# Schematic_v8.net
KiCad netlist of a schematic drawn in EAGLE
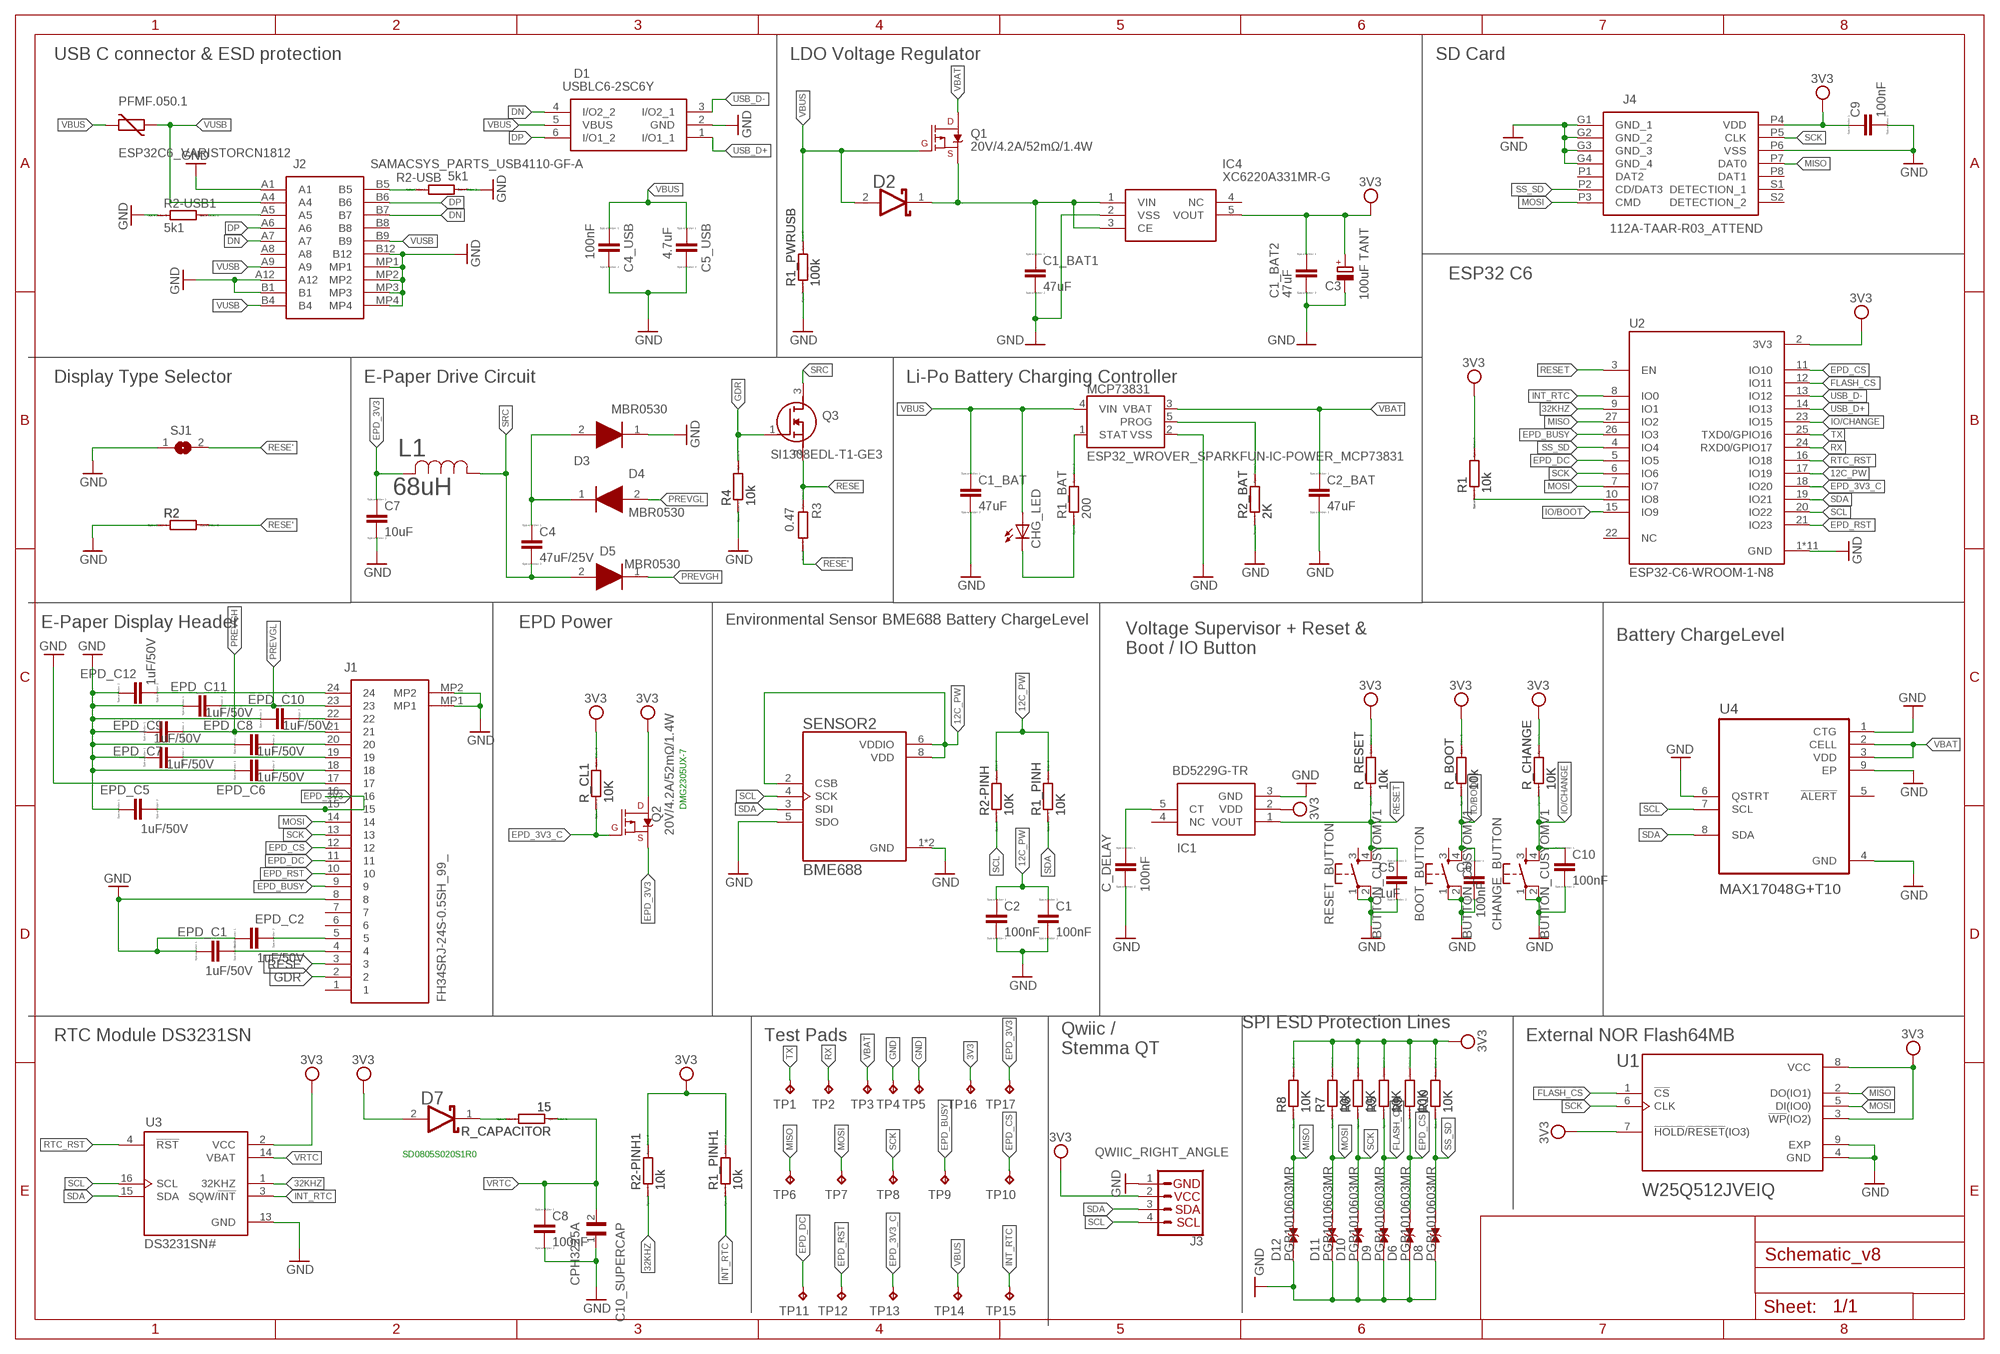
[diagram p0: schematic, sheet 1]

(export (version "E")
  (design (tool "Eeschema 10.0.6"))
  (components
    (comp (ref "BOOT_BUTTON")
      (value "BUTTON_CUSYOMV1")
      (footprint "eagle-import:MYBUTTON")
      (libsource (lib "eagle-import") (part "BUTTON_CUSYOMV1"))
    )
    (comp (ref "C1")
      (value "100nF")
      (footprint "eagle-import:EAGLE-LTSPICE_C0402")
      (libsource (lib "eagle-import") (part "EAGLE-LTSPICE_CC0402"))
    )
    (comp (ref "C1_BAT")
      (value "47uF")
      (footprint "eagle-import:EAGLE-LTSPICE_C0402")
      (libsource (lib "eagle-import") (part "EAGLE-LTSPICE_CC0402"))
    )
    (comp (ref "C1_BAT1")
      (value "47uF")
      (footprint "eagle-import:EAGLE-LTSPICE_C0402")
      (libsource (lib "eagle-import") (part "EAGLE-LTSPICE_CC0402"))
    )
    (comp (ref "C1_BAT2")
      (value "47uF")
      (footprint "eagle-import:EAGLE-LTSPICE_C0402")
      (libsource (lib "eagle-import") (part "EAGLE-LTSPICE_CC0402"))
    )
    (comp (ref "C2")
      (value "100nF")
      (footprint "eagle-import:EAGLE-LTSPICE_C0402")
      (libsource (lib "eagle-import") (part "EAGLE-LTSPICE_CC0402"))
    )
    (comp (ref "C2_BAT")
      (value "47uF")
      (footprint "eagle-import:EAGLE-LTSPICE_C0402")
      (libsource (lib "eagle-import") (part "EAGLE-LTSPICE_CC0402"))
    )
    (comp (ref "C3")
      (value "100uF TANT")
      (footprint "eagle-import:RCL_CT3528")
      (libsource (lib "eagle-import") (part "RCL_CPOL-EUCT3528"))
    )
    (comp (ref "C4")
      (value "47uF/25V")
      (footprint "eagle-import:EAGLE-LTSPICE_C0402")
      (libsource (lib "eagle-import") (part "EAGLE-LTSPICE_CC0402"))
    )
    (comp (ref "C4_USB")
      (value "100nF")
      (footprint "eagle-import:EAGLE-LTSPICE_C0402")
      (libsource (lib "eagle-import") (part "EAGLE-LTSPICE_CC0402"))
    )
    (comp (ref "C5")
      (value "1uF")
      (footprint "eagle-import:EAGLE-LTSPICE_C0402")
      (libsource (lib "eagle-import") (part "EAGLE-LTSPICE_CC0402"))
    )
    (comp (ref "C5_USB")
      (value "4.7uF")
      (footprint "eagle-import:EAGLE-LTSPICE_C0402")
      (libsource (lib "eagle-import") (part "EAGLE-LTSPICE_CC0402"))
    )
    (comp (ref "C6")
      (value "100nF")
      (footprint "eagle-import:EAGLE-LTSPICE_C0402")
      (libsource (lib "eagle-import") (part "EAGLE-LTSPICE_CC0402"))
    )
    (comp (ref "C7")
      (value "10uF")
      (footprint "eagle-import:EAGLE-LTSPICE_C0402")
      (libsource (lib "eagle-import") (part "EAGLE-LTSPICE_CC0402"))
    )
    (comp (ref "C8")
      (value "100nF")
      (footprint "eagle-import:EAGLE-LTSPICE_C0402")
      (libsource (lib "eagle-import") (part "EAGLE-LTSPICE_CC0402"))
    )
    (comp (ref "C9")
      (value "100nF")
      (footprint "eagle-import:EAGLE-LTSPICE_C0402")
      (libsource (lib "eagle-import") (part "EAGLE-LTSPICE_CC0402"))
    )
    (comp (ref "C10")
      (value "100nF")
      (footprint "eagle-import:EAGLE-LTSPICE_C0402")
      (libsource (lib "eagle-import") (part "EAGLE-LTSPICE_CC0402"))
    )
    (comp (ref "C10_SUPERCAP")
      (value "CPH3225A")
      (footprint "eagle-import:CAPCP3225X100N")
      (fields (field (name "MF") "Seiko Instruments"))
      (libsource (lib "eagle-import") (part "CPH3225A"))
    )
    (comp (ref "CHANGE_BUTTON")
      (value "BUTTON_CUSYOMV1")
      (footprint "eagle-import:MYBUTTON")
      (libsource (lib "eagle-import") (part "BUTTON_CUSYOMV1"))
    )
    (comp (ref "CHG_LED")
      (value "ADAFRUIT_LEDCHIP-LED0603")
      (footprint "eagle-import:ADAFRUIT_CHIP-LED0603")
      (libsource (lib "eagle-import") (part "ADAFRUIT_LEDCHIP-LED0603"))
    )
    (comp (ref "C_DELAY")
      (value "100nF")
      (footprint "eagle-import:EAGLE-LTSPICE_C0402")
      (libsource (lib "eagle-import") (part "EAGLE-LTSPICE_CC0402"))
    )
    (comp (ref "D1")
      (value "USBLC6-2SC6Y")
      (footprint "eagle-import:SOT95P280X145-6N")
      (fields (field (name "MF") "STMicroelectronics"))
      (libsource (lib "eagle-import") (part "USBLC6-2SC6Y"))
    )
    (comp (ref "D2")
      (value "SD0805S020S1R0")
      (footprint "eagle-import:ESP32_WROVER_AVX---SD0805S020S1R0_AVX_SD0805S020S1R0_0")
      (fields
        (field (name "DIGIKEY_PART_NUMBER") "478-7800-1-ND")
        (field (name "MF") "AVX")
        (field (name "MOUSER_PART_NUMBER") "581-SD0805S020S1R0")
      )
      (libsource (lib "eagle-import") (part "ESP32_WROVER_AVX---SD0805S020S1R0_AVX_SD0805S020S1R0_0_0AVX_SD0805S020S1R0_0_0"))
    )
    (comp (ref "D3")
      (value "MBR0530")
      (footprint "eagle-import:SOD3716X135N")
      (fields (field (name "MF") "ON Semiconductor"))
      (libsource (lib "eagle-import") (part "MBR0530"))
    )
    (comp (ref "D4")
      (value "MBR0530")
      (footprint "eagle-import:SOD3716X135N")
      (fields (field (name "MF") "ON Semiconductor"))
      (libsource (lib "eagle-import") (part "MBR0530"))
    )
    (comp (ref "D5")
      (value "MBR0530")
      (footprint "eagle-import:SOD3716X135N")
      (fields (field (name "MF") "ON Semiconductor"))
      (libsource (lib "eagle-import") (part "MBR0530"))
    )
    (comp (ref "D6")
      (value "PGB1010603MR")
      (footprint "eagle-import:DIOC1608X36N")
      (fields (field (name "MF") "Littelfuse Inc."))
      (libsource (lib "eagle-import") (part "PGB1010603MR"))
    )
    (comp (ref "D7")
      (value "SD0805S020S1R0")
      (footprint "eagle-import:ESP32_WROVER_AVX---SD0805S020S1R0_AVX_SD0805S020S1R0_0")
      (fields
        (field (name "DIGIKEY_PART_NUMBER") "478-7800-1-ND")
        (field (name "MF") "AVX")
        (field (name "MOUSER_PART_NUMBER") "581-SD0805S020S1R0")
      )
      (libsource (lib "eagle-import") (part "ESP32_WROVER_AVX---SD0805S020S1R0_AVX_SD0805S020S1R0_0_0AVX_SD0805S020S1R0_0_0"))
    )
    (comp (ref "D8")
      (value "PGB1010603MR")
      (footprint "eagle-import:DIOC1608X36N")
      (fields (field (name "MF") "Littelfuse Inc."))
      (libsource (lib "eagle-import") (part "PGB1010603MR"))
    )
    (comp (ref "D9")
      (value "PGB1010603MR")
      (footprint "eagle-import:DIOC1608X36N")
      (fields (field (name "MF") "Littelfuse Inc."))
      (libsource (lib "eagle-import") (part "PGB1010603MR"))
    )
    (comp (ref "D10")
      (value "PGB1010603MR")
      (footprint "eagle-import:DIOC1608X36N")
      (fields (field (name "MF") "Littelfuse Inc."))
      (libsource (lib "eagle-import") (part "PGB1010603MR"))
    )
    (comp (ref "D11")
      (value "PGB1010603MR")
      (footprint "eagle-import:DIOC1608X36N")
      (fields (field (name "MF") "Littelfuse Inc."))
      (libsource (lib "eagle-import") (part "PGB1010603MR"))
    )
    (comp (ref "D12")
      (value "PGB1010603MR")
      (footprint "eagle-import:DIOC1608X36N")
      (fields (field (name "MF") "Littelfuse Inc."))
      (libsource (lib "eagle-import") (part "PGB1010603MR"))
    )
    (comp (ref "EPD_C1")
      (value "1uF/50V")
      (footprint "eagle-import:EAGLE-LTSPICE_C0402")
      (libsource (lib "eagle-import") (part "EAGLE-LTSPICE_CC0402"))
    )
    (comp (ref "EPD_C2")
      (value "1uF/50V")
      (footprint "eagle-import:EAGLE-LTSPICE_C0402")
      (libsource (lib "eagle-import") (part "EAGLE-LTSPICE_CC0402"))
    )
    (comp (ref "EPD_C5")
      (value "1uF/50V")
      (footprint "eagle-import:EAGLE-LTSPICE_C0402")
      (libsource (lib "eagle-import") (part "EAGLE-LTSPICE_CC0402"))
    )
    (comp (ref "EPD_C6")
      (value "1uF/50V")
      (footprint "eagle-import:EAGLE-LTSPICE_C0402")
      (libsource (lib "eagle-import") (part "EAGLE-LTSPICE_CC0402"))
    )
    (comp (ref "EPD_C7")
      (value "1uF/50V")
      (footprint "eagle-import:EAGLE-LTSPICE_C0402")
      (libsource (lib "eagle-import") (part "EAGLE-LTSPICE_CC0402"))
    )
    (comp (ref "EPD_C8")
      (value "1uF/50V")
      (footprint "eagle-import:EAGLE-LTSPICE_C0402")
      (libsource (lib "eagle-import") (part "EAGLE-LTSPICE_CC0402"))
    )
    (comp (ref "EPD_C9")
      (value "1uF/50V")
      (footprint "eagle-import:EAGLE-LTSPICE_C0402")
      (libsource (lib "eagle-import") (part "EAGLE-LTSPICE_CC0402"))
    )
    (comp (ref "EPD_C10")
      (value "1uF/50V")
      (footprint "eagle-import:EAGLE-LTSPICE_C0402")
      (libsource (lib "eagle-import") (part "EAGLE-LTSPICE_CC0402"))
    )
    (comp (ref "EPD_C11")
      (value "1uF/50V")
      (footprint "eagle-import:EAGLE-LTSPICE_C0402")
      (libsource (lib "eagle-import") (part "EAGLE-LTSPICE_CC0402"))
    )
    (comp (ref "EPD_C12")
      (value "1uF/50V")
      (footprint "eagle-import:EAGLE-LTSPICE_C0402")
      (libsource (lib "eagle-import") (part "EAGLE-LTSPICE_CC0402"))
    )
    (comp (ref "IC1")
      (value "BD5229G-TR")
      (footprint "eagle-import:SOT95P280X125-5N")
      (fields (field (name "MOUSER_PART_NUMBER") "755-BD5229G-TR"))
      (libsource (lib "eagle-import") (part "BD5229G-TR"))
    )
    (comp (ref "IC4")
      (value "XC6220A331MR-G")
      (footprint "eagle-import:SOT95P280X120-5N")
      (fields (field (name "MOUSER_PART_NUMBER") "865-XC6220A331MR-G"))
      (libsource (lib "eagle-import") (part "XC6220A331MR-G"))
    )
    (comp (ref "J1")
      (value "FH34SRJ-24S-0.5SH_99_")
      (footprint "eagle-import:FH34SRJ24S05SH99")
      (fields
        (field (name "MANUFACTURER_PART_NUMBER") "FH34SRJ-24S-0.5SH(99)")
        (field (name "MOUSER_PART_NUMBER") "798-FH34SRJ24S05SH99")
      )
      (libsource (lib "eagle-import") (part "FH34SRJ-24S-0.5SH_99_"))
    )
    (comp (ref "J2")
      (value "SAMACSYS_PARTS_USB4110-GF-A")
      (footprint "eagle-import:SAMACSYS_PARTS_USB4110GFA")
      (libsource (lib "eagle-import") (part "SAMACSYS_PARTS_USB4110-GF-ASAM"))
    )
    (comp (ref "J3")
      (value "QWIIC_RIGHT_ANGLE")
      (footprint "eagle-import:JST04_1MM_RA")
      (libsource (lib "eagle-import") (part "QWIIC_CONNECTORJS-1MM"))
    )
    (comp (ref "J4")
      (value "112A-TAAR-R03_ATTEND")
      (footprint "eagle-import:112ATAARR03ATTEND")
      (fields (field (name "MANUFACTURER_PART_NUMBER") "112A-TAAR-R03 ATTEND"))
      (libsource (lib "eagle-import") (part "112A-TAAR-R03_ATTEND"))
    )
    (comp (ref "L1")
      (value "68uH")
      (footprint "eagle-import:IND_4828-WE-TPC_WRE")
      (fields
        (field (name "MANUFACTURER_PART_NUMBER") "744043680")
        (field (name "COPYRIGHT") "Copyright (C) 2024 Ultra Librarian. All rights reserved.")
      )
      (libsource (lib "eagle-import") (part "744043680IND_4828-WE-TPC_WRE"))
    )
    (comp (ref "MCP73831")
      (value "ESP32_WROVER_SPARKFUN-IC-POWER_MCP73831")
      (footprint "eagle-import:ESP32_WROVER_SPARKFUN-IC-POWER_SOT23-5")
      (libsource (lib "eagle-import") (part "ESP32_WROVER_SPARKFUN-IC-POWER_MCP73831"))
    )
    (comp (ref "PFMF.050.1")
      (value "ESP32C6_VARISTORCN1812")
      (footprint "eagle-import:ESP32C6_VARISTOR_CT_CN1812")
      (libsource (lib "eagle-import") (part "ESP32C6_VARISTORCN1812"))
    )
    (comp (ref "Q1")
      (value "20V/4.2A/52mΩ/1.4W")
      (footprint "eagle-import:ESP32_WROVER_SPARKFUN-DISCRETESEMI_SOT23-3")
      (libsource (lib "eagle-import") (part "ESP32_WROVER_SPARKFUN-DISCRETESEMI_MOSFET_PCH-DMG2305UX-7"))
    )
    (comp (ref "Q2")
      (value "20V/4.2A/52mΩ/1.4W")
      (footprint "eagle-import:ESP32_WROVER_SPARKFUN-DISCRETESEMI_SOT23-3")
      (libsource (lib "eagle-import") (part "ESP32_WROVER_SPARKFUN-DISCRETESEMI_MOSFET_PCH-DMG2305UX-7"))
    )
    (comp (ref "Q3")
      (value "SI1308EDL-T1-GE3")
      (footprint "eagle-import:SOT65P210X110-3N")
      (fields (field (name "MF") "Vishay Siliconix"))
      (libsource (lib "eagle-import") (part "SI1308EDL-T1-GE3"))
    )
    (comp (ref "R1")
      (value "10k")
      (footprint "eagle-import:ESP32_WROVER_EAGLE-LTSPICE_R0402")
      (libsource (lib "eagle-import") (part "ESP32_WROVER_EAGLE-LTSPICE_RR0402"))
    )
    (comp (ref "R1_BAT")
      (value "200")
      (footprint "eagle-import:ESP32_WROVER_EAGLE-LTSPICE_R0402")
      (libsource (lib "eagle-import") (part "ESP32_WROVER_EAGLE-LTSPICE_RR0402"))
    )
    (comp (ref "R1_PINH")
      (value "10K")
      (footprint "eagle-import:ESP32_WROVER_EAGLE-LTSPICE_R0402")
      (libsource (lib "eagle-import") (part "ESP32_WROVER_EAGLE-LTSPICE_RR0402"))
    )
    (comp (ref "R1_PINH1")
      (value "10k")
      (footprint "eagle-import:ESP32_WROVER_EAGLE-LTSPICE_R0402")
      (libsource (lib "eagle-import") (part "ESP32_WROVER_EAGLE-LTSPICE_RR0402"))
    )
    (comp (ref "R1_PWRUSB")
      (value "100k")
      (footprint "eagle-import:ESP32_WROVER_EAGLE-LTSPICE_R0402")
      (libsource (lib "eagle-import") (part "ESP32_WROVER_EAGLE-LTSPICE_RR0402"))
    )
    (comp (ref "R2")
      (value "ESP32_WROVER_EAGLE-LTSPICE_RR0402")
      (footprint "eagle-import:ESP32_WROVER_EAGLE-LTSPICE_R0402")
      (libsource (lib "eagle-import") (part "ESP32_WROVER_EAGLE-LTSPICE_RR0402"))
    )
    (comp (ref "R2-PINH")
      (value "10K")
      (footprint "eagle-import:ESP32_WROVER_EAGLE-LTSPICE_R0402")
      (libsource (lib "eagle-import") (part "ESP32_WROVER_EAGLE-LTSPICE_RR0402"))
    )
    (comp (ref "R2-PINH1")
      (value "10k")
      (footprint "eagle-import:ESP32_WROVER_EAGLE-LTSPICE_R0402")
      (libsource (lib "eagle-import") (part "ESP32_WROVER_EAGLE-LTSPICE_RR0402"))
    )
    (comp (ref "R2-USB")
      (value "5k1")
      (footprint "eagle-import:ESP32_WROVER_EAGLE-LTSPICE_R0402")
      (libsource (lib "eagle-import") (part "ESP32_WROVER_EAGLE-LTSPICE_RR0402"))
    )
    (comp (ref "R2-USB1")
      (value "5k1")
      (footprint "eagle-import:ESP32_WROVER_EAGLE-LTSPICE_R0402")
      (libsource (lib "eagle-import") (part "ESP32_WROVER_EAGLE-LTSPICE_RR0402"))
    )
    (comp (ref "R2_BAT")
      (value "2K")
      (footprint "eagle-import:ESP32_WROVER_EAGLE-LTSPICE_R0402")
      (libsource (lib "eagle-import") (part "ESP32_WROVER_EAGLE-LTSPICE_RR0402"))
    )
    (comp (ref "R3")
      (value "0.47")
      (footprint "eagle-import:ESP32_WROVER_EAGLE-LTSPICE_R0402")
      (libsource (lib "eagle-import") (part "ESP32_WROVER_EAGLE-LTSPICE_RR0402"))
    )
    (comp (ref "R4")
      (value "10k")
      (footprint "eagle-import:ESP32_WROVER_EAGLE-LTSPICE_R0402")
      (libsource (lib "eagle-import") (part "ESP32_WROVER_EAGLE-LTSPICE_RR0402"))
    )
    (comp (ref "R5")
      (value "10K")
      (footprint "eagle-import:ESP32_WROVER_EAGLE-LTSPICE_R0402")
      (libsource (lib "eagle-import") (part "ESP32_WROVER_EAGLE-LTSPICE_RR0402"))
    )
    (comp (ref "R6")
      (value "10K")
      (footprint "eagle-import:ESP32_WROVER_EAGLE-LTSPICE_R0402")
      (libsource (lib "eagle-import") (part "ESP32_WROVER_EAGLE-LTSPICE_RR0402"))
    )
    (comp (ref "R7")
      (value "10K")
      (footprint "eagle-import:ESP32_WROVER_EAGLE-LTSPICE_R0402")
      (libsource (lib "eagle-import") (part "ESP32_WROVER_EAGLE-LTSPICE_RR0402"))
    )
    (comp (ref "R8")
      (value "10K")
      (footprint "eagle-import:ESP32_WROVER_EAGLE-LTSPICE_R0402")
      (libsource (lib "eagle-import") (part "ESP32_WROVER_EAGLE-LTSPICE_RR0402"))
    )
    (comp (ref "R9")
      (value "10K")
      (footprint "eagle-import:ESP32_WROVER_EAGLE-LTSPICE_R0402")
      (libsource (lib "eagle-import") (part "ESP32_WROVER_EAGLE-LTSPICE_RR0402"))
    )
    (comp (ref "R10")
      (value "10K")
      (footprint "eagle-import:ESP32_WROVER_EAGLE-LTSPICE_R0402")
      (libsource (lib "eagle-import") (part "ESP32_WROVER_EAGLE-LTSPICE_RR0402"))
    )
    (comp (ref "RESET_BUTTON")
      (value "BUTTON_CUSYOMV1")
      (footprint "eagle-import:MYBUTTON")
      (libsource (lib "eagle-import") (part "BUTTON_CUSYOMV1"))
    )
    (comp (ref "R_BOOT")
      (value "10k")
      (footprint "eagle-import:ESP32_WROVER_EAGLE-LTSPICE_R0402")
      (libsource (lib "eagle-import") (part "ESP32_WROVER_EAGLE-LTSPICE_RR0402"))
    )
    (comp (ref "R_CAPACITOR")
      (value "15")
      (footprint "eagle-import:ESP32_WROVER_EAGLE-LTSPICE_R0402")
      (libsource (lib "eagle-import") (part "ESP32_WROVER_EAGLE-LTSPICE_RR0402"))
    )
    (comp (ref "R_CHANGE")
      (value "10K")
      (footprint "eagle-import:ESP32_WROVER_EAGLE-LTSPICE_R0402")
      (libsource (lib "eagle-import") (part "ESP32_WROVER_EAGLE-LTSPICE_RR0402"))
    )
    (comp (ref "R_CL1")
      (value "10K")
      (footprint "eagle-import:ESP32_WROVER_EAGLE-LTSPICE_R0402")
      (libsource (lib "eagle-import") (part "ESP32_WROVER_EAGLE-LTSPICE_RR0402"))
    )
    (comp (ref "R_RESET")
      (value "10k")
      (footprint "eagle-import:ESP32_WROVER_EAGLE-LTSPICE_R0402")
      (libsource (lib "eagle-import") (part "ESP32_WROVER_EAGLE-LTSPICE_RR0402"))
    )
    (comp (ref "SENSOR2")
      (value "BME688")
      (footprint "eagle-import:ESP32_WROVER_BME680_PSON80P300X300X100-8N")
      (fields (field (name "MF") "Bosch Sensortec") (field (name "MP") "BME680"))
      (libsource (lib "eagle-import") (part "ESP32_WROVER_BME680_BME680"))
    )
    (comp (ref "SJ1") (value "SJ") (footprint "eagle-import:SJ") (libsource (lib "eagle-import") (part "SJ")))
    (comp (ref "TP1")
      (value "TPTP20R")
      (footprint "eagle-import:TP20R")
      (libsource (lib "eagle-import") (part "TPTP20R"))
    )
    (comp (ref "TP2")
      (value "TPTP20R")
      (footprint "eagle-import:TP20R")
      (libsource (lib "eagle-import") (part "TPTP20R"))
    )
    (comp (ref "TP3")
      (value "TPTP20R")
      (footprint "eagle-import:TP20R")
      (libsource (lib "eagle-import") (part "TPTP20R"))
    )
    (comp (ref "TP4")
      (value "TPTP20R")
      (footprint "eagle-import:TP20R")
      (libsource (lib "eagle-import") (part "TPTP20R"))
    )
    (comp (ref "TP5")
      (value "TPTP20R")
      (footprint "eagle-import:TP20R")
      (libsource (lib "eagle-import") (part "TPTP20R"))
    )
    (comp (ref "TP6")
      (value "TPTP20R")
      (footprint "eagle-import:TP20R")
      (libsource (lib "eagle-import") (part "TPTP20R"))
    )
    (comp (ref "TP7")
      (value "TPTP20R")
      (footprint "eagle-import:TP20R")
      (libsource (lib "eagle-import") (part "TPTP20R"))
    )
    (comp (ref "TP8")
      (value "TPTP20R")
      (footprint "eagle-import:TP20R")
      (libsource (lib "eagle-import") (part "TPTP20R"))
    )
    (comp (ref "TP9")
      (value "TPTP20R")
      (footprint "eagle-import:TP20R")
      (libsource (lib "eagle-import") (part "TPTP20R"))
    )
    (comp (ref "TP10")
      (value "TPTP20R")
      (footprint "eagle-import:TP20R")
      (libsource (lib "eagle-import") (part "TPTP20R"))
    )
    (comp (ref "TP11")
      (value "TPTP20R")
      (footprint "eagle-import:TP20R")
      (libsource (lib "eagle-import") (part "TPTP20R"))
    )
    (comp (ref "TP12")
      (value "TPTP20R")
      (footprint "eagle-import:TP20R")
      (libsource (lib "eagle-import") (part "TPTP20R"))
    )
    (comp (ref "TP13")
      (value "TPTP20R")
      (footprint "eagle-import:TP20R")
      (libsource (lib "eagle-import") (part "TPTP20R"))
    )
    (comp (ref "TP14")
      (value "TPTP20R")
      (footprint "eagle-import:TP20R")
      (libsource (lib "eagle-import") (part "TPTP20R"))
    )
    (comp (ref "TP15")
      (value "TPTP20R")
      (footprint "eagle-import:TP20R")
      (libsource (lib "eagle-import") (part "TPTP20R"))
    )
    (comp (ref "TP16")
      (value "TPTP20R")
      (footprint "eagle-import:TP20R")
      (libsource (lib "eagle-import") (part "TPTP20R"))
    )
    (comp (ref "TP17")
      (value "TPTP20R")
      (footprint "eagle-import:TP20R")
      (libsource (lib "eagle-import") (part "TPTP20R"))
    )
    (comp (ref "U1")
      (value "W25Q512JVEIQ")
      (footprint "eagle-import:SON127P600X800X80-9N")
      (fields (field (name "MF") "Winbond Electronics"))
      (libsource (lib "eagle-import") (part "W25Q512JVEIQ"))
    )
    (comp (ref "U2")
      (value "ESP32-C6-WROOM-1-N8")
      (footprint "eagle-import:XCVR_ESP32-C6-WROOM-1-N8")
      (fields (field (name "MF") "Espressif Systems"))
      (libsource (lib "eagle-import") (part "ESP32-C6-WROOM-1-N8"))
    )
    (comp (ref "U3")
      (value "DS3231SN#")
      (footprint "eagle-import:SOIC127P1032X265-16N")
      (fields (field (name "MF") "Analog Devices"))
      (libsource (lib "eagle-import") (part "DS3231SN#"))
    )
    (comp (ref "U4")
      (value "MAX17048G+T10")
      (footprint "eagle-import:SON50P200X200X80-9N")
      (fields (field (name "MF") "Analog Devices"))
      (libsource (lib "eagle-import") (part "MAX17048G+T10"))
    )
  )
  (nets
    (net (code "1") (name "3V3") (class "Default")
      (node (ref "C1_BAT2") (pin "1") (pinfunction "1_1") (pintype "passive"))
      (node (ref "C3") (pin "+") (pinfunction "+_+") (pintype "passive"))
      (node (ref "C9") (pin "1") (pinfunction "1_1") (pintype "passive"))
      (node (ref "D7") (pin "2") (pinfunction "ANODE_2") (pintype "bidirectional"))
      (node (ref "IC1") (pin "2") (pinfunction "VDD_2") (pintype "bidirectional"))
      (node (ref "IC4") (pin "5") (pinfunction "VOUT_5") (pintype "bidirectional"))
      (node (ref "J3") (pin "2") (pinfunction "2_2") (pintype "power_in"))
      (node (ref "J4") (pin "P4") (pinfunction "VDD_P4") (pintype "bidirectional"))
      (node (ref "Q2") (pin "3") (pinfunction "D_3") (pintype "bidirectional"))
      (node (ref "R1") (pin "2") (pinfunction "2_2") (pintype "passive"))
      (node (ref "R10") (pin "2") (pinfunction "2_2") (pintype "passive"))
      (node (ref "R1_PINH1") (pin "2") (pinfunction "2_2") (pintype "passive"))
      (node (ref "R2-PINH1") (pin "2") (pinfunction "2_2") (pintype "passive"))
      (node (ref "R5") (pin "2") (pinfunction "2_2") (pintype "passive"))
      (node (ref "R6") (pin "2") (pinfunction "2_2") (pintype "passive"))
      (node (ref "R7") (pin "2") (pinfunction "2_2") (pintype "passive"))
      (node (ref "R8") (pin "2") (pinfunction "2_2") (pintype "passive"))
      (node (ref "R9") (pin "2") (pinfunction "2_2") (pintype "passive"))
      (node (ref "R_BOOT") (pin "2") (pinfunction "2_2") (pintype "passive"))
      (node (ref "R_CHANGE") (pin "2") (pinfunction "2_2") (pintype "passive"))
      (node (ref "R_CL1") (pin "2") (pinfunction "2_2") (pintype "passive"))
      (node (ref "R_RESET") (pin "2") (pinfunction "2_2") (pintype "passive"))
      (node (ref "TP16") (pin "TP") (pinfunction "TP_TP") (pintype "input"))
      (node (ref "U1") (pin "3") (pinfunction "~{WP}(IO2)_3") (pintype "bidirectional"))
      (node (ref "U1") (pin "7") (pinfunction "~{HOLD}/~{RESET}(IO3)_7") (pintype "bidirectional"))
      (node (ref "U1") (pin "8") (pinfunction "VCC_8") (pintype "power_in"))
      (node (ref "U2") (pin "2") (pinfunction "3V3_2") (pintype "power_in"))
      (node (ref "U3") (pin "2") (pinfunction "VCC_2") (pintype "power_in"))
    )
    (net (code "2") (name "12C_PW") (class "Default")
      (node (ref "C1") (pin "1") (pinfunction "1_1") (pintype "passive"))
      (node (ref "C2") (pin "1") (pinfunction "1_1") (pintype "passive"))
      (node (ref "R1_PINH") (pin "2") (pinfunction "2_2") (pintype "passive"))
      (node (ref "R2-PINH") (pin "2") (pinfunction "2_2") (pintype "passive"))
      (node (ref "SENSOR2") (pin "2") (pinfunction "CSB_2") (pintype "input"))
      (node (ref "SENSOR2") (pin "6") (pinfunction "VDDIO_6") (pintype "power_in"))
      (node (ref "SENSOR2") (pin "8") (pinfunction "VDD_8") (pintype "power_in"))
      (node (ref "U2") (pin "16") (pinfunction "IO18_16") (pintype "bidirectional"))
    )
    (net (code "3") (name "32KHZ") (class "Default")
      (node (ref "R2-PINH1") (pin "1") (pinfunction "1_1") (pintype "passive"))
      (node (ref "U2") (pin "9") (pinfunction "IO1_9") (pintype "bidirectional"))
      (node (ref "U3") (pin "1") (pinfunction "32KHZ_1") (pintype "output"))
    )
    (net (code "4") (name "DN") (class "Default")
      (node (ref "D1") (pin "4") (pinfunction "I/O2_2_4") (pintype "bidirectional"))
      (node (ref "J2") (pin "A7") (pinfunction "A7_A7") (pintype "bidirectional"))
      (node (ref "J2") (pin "B7") (pinfunction "B7_B7") (pintype "bidirectional"))
    )
    (net (code "5") (name "DP") (class "Default")
      (node (ref "D1") (pin "6") (pinfunction "I/O1_2_6") (pintype "bidirectional"))
      (node (ref "J2") (pin "A6") (pinfunction "A6_A6") (pintype "bidirectional"))
      (node (ref "J2") (pin "B6") (pinfunction "B6_B6") (pintype "bidirectional"))
    )
    (net (code "6") (name "EPD_3V3") (class "Default")
      (node (ref "C7") (pin "1") (pinfunction "1_1") (pintype "passive"))
      (node (ref "EPD_C5") (pin "2") (pinfunction "2_2") (pintype "passive"))
      (node (ref "J1") (pin "15") (pinfunction "15_15") (pintype "bidirectional"))
      (node (ref "J1") (pin "16") (pinfunction "16_16") (pintype "bidirectional"))
      (node (ref "L1") (pin "2") (pinfunction "2_2") (pintype "passive"))
      (node (ref "Q2") (pin "2") (pinfunction "S_2") (pintype "bidirectional"))
      (node (ref "TP17") (pin "TP") (pinfunction "TP_TP") (pintype "input"))
    )
    (net (code "7") (name "EPD_3V3_C") (class "Default")
      (node (ref "Q2") (pin "1") (pinfunction "G_1") (pintype "bidirectional"))
      (node (ref "R_CL1") (pin "1") (pinfunction "1_1") (pintype "passive"))
      (node (ref "TP13") (pin "TP") (pinfunction "TP_TP") (pintype "input"))
      (node (ref "U2") (pin "18") (pinfunction "IO20_18") (pintype "bidirectional"))
    )
    (net (code "8") (name "EPD_BUSY") (class "Default")
      (node (ref "J1") (pin "9") (pinfunction "9_9") (pintype "bidirectional"))
      (node (ref "TP9") (pin "TP") (pinfunction "TP_TP") (pintype "input"))
      (node (ref "U2") (pin "26") (pinfunction "IO3_26") (pintype "bidirectional"))
    )
    (net (code "9") (name "EPD_CS") (class "Default")
      (node (ref "D6") (pin "2") (pinfunction "2_2") (pintype "passive"))
      (node (ref "J1") (pin "12") (pinfunction "12_12") (pintype "bidirectional"))
      (node (ref "R9") (pin "1") (pinfunction "1_1") (pintype "passive"))
      (node (ref "TP10") (pin "TP") (pinfunction "TP_TP") (pintype "input"))
      (node (ref "U2") (pin "11") (pinfunction "IO10_11") (pintype "bidirectional"))
    )
    (net (code "10") (name "EPD_DC") (class "Default")
      (node (ref "J1") (pin "11") (pinfunction "11_11") (pintype "bidirectional"))
      (node (ref "TP11") (pin "TP") (pinfunction "TP_TP") (pintype "input"))
      (node (ref "U2") (pin "5") (pinfunction "IO5_5") (pintype "bidirectional"))
    )
    (net (code "11") (name "EPD_RST") (class "Default")
      (node (ref "J1") (pin "10") (pinfunction "10_10") (pintype "bidirectional"))
      (node (ref "TP12") (pin "TP") (pinfunction "TP_TP") (pintype "input"))
      (node (ref "U2") (pin "21") (pinfunction "IO23_21") (pintype "bidirectional"))
    )
    (net (code "12") (name "FLASH_CS") (class "Default")
      (node (ref "D9") (pin "2") (pinfunction "2_2") (pintype "passive"))
      (node (ref "R5") (pin "1") (pinfunction "1_1") (pintype "passive"))
      (node (ref "U1") (pin "1") (pinfunction "~{CS}_1") (pintype "input"))
      (node (ref "U2") (pin "12") (pinfunction "IO11_12") (pintype "bidirectional"))
    )
    (net (code "13") (name "GDR") (class "Default")
      (node (ref "J1") (pin "2") (pinfunction "2_2") (pintype "bidirectional"))
      (node (ref "Q3") (pin "1") (pinfunction "G_1") (pintype "bidirectional"))
      (node (ref "R4") (pin "2") (pinfunction "2_2") (pintype "passive"))
    )
    (net (code "14") (name "GND") (class "Default")
      (node (ref "BOOT_BUTTON") (pin "1") (pinfunction "1_1") (pintype "passive"))
      (node (ref "BOOT_BUTTON") (pin "2") (pinfunction "2_2") (pintype "passive"))
      (node (ref "C1") (pin "2") (pinfunction "2_2") (pintype "passive"))
      (node (ref "C10") (pin "2") (pinfunction "2_2") (pintype "passive"))
      (node (ref "C10_SUPERCAP") (pin "1") (pinfunction "1_1") (pintype "passive"))
      (node (ref "C1_BAT") (pin "2") (pinfunction "2_2") (pintype "passive"))
      (node (ref "C1_BAT1") (pin "2") (pinfunction "2_2") (pintype "passive"))
      (node (ref "C1_BAT2") (pin "2") (pinfunction "2_2") (pintype "passive"))
      (node (ref "C2") (pin "2") (pinfunction "2_2") (pintype "passive"))
      (node (ref "C2_BAT") (pin "2") (pinfunction "2_2") (pintype "passive"))
      (node (ref "C3") (pin "-") (pinfunction "-_-") (pintype "passive"))
      (node (ref "C4_USB") (pin "2") (pinfunction "2_2") (pintype "passive"))
      (node (ref "C5") (pin "2") (pinfunction "2_2") (pintype "passive"))
      (node (ref "C5_USB") (pin "2") (pinfunction "2_2") (pintype "passive"))
      (node (ref "C6") (pin "2") (pinfunction "2_2") (pintype "passive"))
      (node (ref "C7") (pin "2") (pinfunction "2_2") (pintype "passive"))
      (node (ref "C8") (pin "2") (pinfunction "2_2") (pintype "passive"))
      (node (ref "C9") (pin "2") (pinfunction "2_2") (pintype "passive"))
      (node (ref "CHANGE_BUTTON") (pin "1") (pinfunction "1_1") (pintype "passive"))
      (node (ref "CHANGE_BUTTON") (pin "2") (pinfunction "2_2") (pintype "passive"))
      (node (ref "C_DELAY") (pin "2") (pinfunction "2_2") (pintype "passive"))
      (node (ref "D1") (pin "2") (pinfunction "GND_2") (pintype "bidirectional"))
      (node (ref "D10") (pin "1") (pinfunction "1_1") (pintype "passive"))
      (node (ref "D11") (pin "1") (pinfunction "1_1") (pintype "passive"))
      (node (ref "D12") (pin "1") (pinfunction "1_1") (pintype "passive"))
      (node (ref "D3") (pin "1") (pinfunction "K_1") (pintype "bidirectional"))
      (node (ref "D6") (pin "1") (pinfunction "1_1") (pintype "passive"))
      (node (ref "D8") (pin "1") (pinfunction "1_1") (pintype "passive"))
      (node (ref "D9") (pin "1") (pinfunction "1_1") (pintype "passive"))
      (node (ref "EPD_C1") (pin "1") (pinfunction "1_1") (pintype "passive"))
      (node (ref "EPD_C10") (pin "1") (pinfunction "1_1") (pintype "passive"))
      (node (ref "EPD_C11") (pin "1") (pinfunction "1_1") (pintype "passive"))
      (node (ref "EPD_C12") (pin "1") (pinfunction "1_1") (pintype "passive"))
      (node (ref "EPD_C2") (pin "1") (pinfunction "1_1") (pintype "passive"))
      (node (ref "EPD_C5") (pin "1") (pinfunction "1_1") (pintype "passive"))
      (node (ref "EPD_C6") (pin "1") (pinfunction "1_1") (pintype "passive"))
      (node (ref "EPD_C7") (pin "1") (pinfunction "1_1") (pintype "passive"))
      (node (ref "EPD_C8") (pin "1") (pinfunction "1_1") (pintype "passive"))
      (node (ref "EPD_C9") (pin "1") (pinfunction "1_1") (pintype "passive"))
      (node (ref "IC1") (pin "3") (pinfunction "GND_3") (pintype "bidirectional"))
      (node (ref "IC4") (pin "2") (pinfunction "VSS_2") (pintype "bidirectional"))
      (node (ref "J1") (pin "17") (pinfunction "17_17") (pintype "bidirectional"))
      (node (ref "J1") (pin "8") (pinfunction "8_8") (pintype "bidirectional"))
      (node (ref "J1") (pin "MP1") (pinfunction "MP1_MP1") (pintype "bidirectional"))
      (node (ref "J1") (pin "MP2") (pinfunction "MP2_MP2") (pintype "bidirectional"))
      (node (ref "J2") (pin "A1") (pinfunction "A1_A1") (pintype "bidirectional"))
      (node (ref "J2") (pin "A12") (pinfunction "A12_A12") (pintype "bidirectional"))
      (node (ref "J2") (pin "B1") (pinfunction "B1_B1") (pintype "bidirectional"))
      (node (ref "J2") (pin "B12") (pinfunction "B12_B12") (pintype "bidirectional"))
      (node (ref "J2") (pin "MP1") (pinfunction "MP1_MP1") (pintype "bidirectional"))
      (node (ref "J2") (pin "MP2") (pinfunction "MP2_MP2") (pintype "bidirectional"))
      (node (ref "J2") (pin "MP3") (pinfunction "MP3_MP3") (pintype "bidirectional"))
      (node (ref "J2") (pin "MP4") (pinfunction "MP4_MP4") (pintype "bidirectional"))
      (node (ref "J3") (pin "1") (pinfunction "1_1") (pintype "power_in"))
      (node (ref "J4") (pin "G1") (pinfunction "GND_1_G1") (pintype "bidirectional"))
      (node (ref "J4") (pin "G2") (pinfunction "GND_2_G2") (pintype "bidirectional"))
      (node (ref "J4") (pin "G3") (pinfunction "GND_3_G3") (pintype "bidirectional"))
      (node (ref "J4") (pin "G4") (pinfunction "GND_4_G4") (pintype "bidirectional"))
      (node (ref "J4") (pin "P6") (pinfunction "VSS_P6") (pintype "bidirectional"))
      (node (ref "MCP73831") (pin "2") (pinfunction "VSS_2") (pintype "power_in"))
      (node (ref "R1_PWRUSB") (pin "1") (pinfunction "1_1") (pintype "passive"))
      (node (ref "R2") (pin "1") (pinfunction "1_1") (pintype "passive"))
      (node (ref "R2-USB") (pin "2") (pinfunction "2_2") (pintype "passive"))
      (node (ref "R2-USB1") (pin "1") (pinfunction "1_1") (pintype "passive"))
      (node (ref "R2_BAT") (pin "1") (pinfunction "1_1") (pintype "passive"))
      (node (ref "R4") (pin "1") (pinfunction "1_1") (pintype "passive"))
      (node (ref "RESET_BUTTON") (pin "1") (pinfunction "1_1") (pintype "passive"))
      (node (ref "RESET_BUTTON") (pin "2") (pinfunction "2_2") (pintype "passive"))
      (node (ref "SENSOR2") (pin "1") (pinfunction "GND_1") (pintype "power_in"))
      (node (ref "SENSOR2") (pin "5") (pinfunction "SDO_5") (pintype "bidirectional"))
      (node (ref "SENSOR2") (pin "7") (pinfunction "GND_7") (pintype "power_in"))
      (node (ref "SJ1") (pin "1") (pinfunction "1_1") (pintype "passive"))
      (node (ref "TP4") (pin "TP") (pinfunction "TP_TP") (pintype "input"))
      (node (ref "TP5") (pin "TP") (pinfunction "TP_TP") (pintype "input"))
      (node (ref "U1") (pin "4") (pinfunction "GND_4") (pintype "power_in"))
      (node (ref "U1") (pin "9") (pinfunction "EXP_9") (pintype "passive"))
      (node (ref "U2") (pin "1") (pinfunction "GND_1") (pintype "power_in"))
      (node (ref "U2") (pin "28") (pinfunction "GND_28") (pintype "power_in"))
      (node (ref "U2") (pin "29_1") (pinfunction "GND_29_1") (pintype "power_in"))
      (node (ref "U2") (pin "29_2") (pinfunction "GND_29_2") (pintype "power_in"))
      (node (ref "U2") (pin "29_3") (pinfunction "GND_29_3") (pintype "power_in"))
      (node (ref "U2") (pin "29_4") (pinfunction "GND_29_4") (pintype "power_in"))
      (node (ref "U2") (pin "29_5") (pinfunction "GND_29_5") (pintype "power_in"))
      (node (ref "U2") (pin "29_6") (pinfunction "GND_29_6") (pintype "power_in"))
      (node (ref "U2") (pin "29_7") (pinfunction "GND_29_7") (pintype "power_in"))
      (node (ref "U2") (pin "29_8") (pinfunction "GND_29_8") (pintype "power_in"))
      (node (ref "U2") (pin "29_9") (pinfunction "GND_29_9") (pintype "power_in"))
      (node (ref "U3") (pin "13") (pinfunction "GND_13") (pintype "power_in"))
      (node (ref "U4") (pin "1") (pinfunction "CTG_1") (pintype "power_in"))
      (node (ref "U4") (pin "4") (pinfunction "GND_4") (pintype "power_in"))
      (node (ref "U4") (pin "6") (pinfunction "QSTRT_6") (pintype "input"))
      (node (ref "U4") (pin "9") (pinfunction "EP_9") (pintype "power_in"))
    )
    (net (code "15") (name "INT_RTC") (class "Default")
      (node (ref "R1_PINH1") (pin "1") (pinfunction "1_1") (pintype "passive"))
      (node (ref "TP15") (pin "TP") (pinfunction "TP_TP") (pintype "input"))
      (node (ref "U2") (pin "8") (pinfunction "IO0_8") (pintype "bidirectional"))
      (node (ref "U3") (pin "3") (pinfunction "SQW/~{INT}_3") (pintype "output"))
    )
    (net (code "16") (name "IO{slash}BOOT") (class "Default")
      (node (ref "BOOT_BUTTON") (pin "4") (pinfunction "4_4") (pintype "passive"))
      (node (ref "C6") (pin "1") (pinfunction "1_1") (pintype "passive"))
      (node (ref "R_BOOT") (pin "1") (pinfunction "1_1") (pintype "passive"))
      (node (ref "U2") (pin "15") (pinfunction "IO9_15") (pintype "bidirectional"))
    )
    (net (code "17") (name "IO{slash}CHANGE") (class "Default")
      (node (ref "C10") (pin "1") (pinfunction "1_1") (pintype "passive"))
      (node (ref "CHANGE_BUTTON") (pin "4") (pinfunction "4_4") (pintype "passive"))
      (node (ref "R_CHANGE") (pin "1") (pinfunction "1_1") (pintype "passive"))
      (node (ref "U2") (pin "23") (pinfunction "IO15_23") (pintype "bidirectional"))
    )
    (net (code "18") (name "MISO") (class "Default")
      (node (ref "D12") (pin "2") (pinfunction "2_2") (pintype "passive"))
      (node (ref "J4") (pin "P7") (pinfunction "DAT0_P7") (pintype "bidirectional"))
      (node (ref "R8") (pin "1") (pinfunction "1_1") (pintype "passive"))
      (node (ref "TP6") (pin "TP") (pinfunction "TP_TP") (pintype "input"))
      (node (ref "U1") (pin "2") (pinfunction "DO(IO1)_2") (pintype "bidirectional"))
      (node (ref "U2") (pin "27") (pinfunction "IO2_27") (pintype "bidirectional"))
    )
    (net (code "19") (name "MOSI") (class "Default")
      (node (ref "D11") (pin "2") (pinfunction "2_2") (pintype "passive"))
      (node (ref "J1") (pin "14") (pinfunction "14_14") (pintype "bidirectional"))
      (node (ref "J4") (pin "P3") (pinfunction "CMD_P3") (pintype "bidirectional"))
      (node (ref "R7") (pin "1") (pinfunction "1_1") (pintype "passive"))
      (node (ref "TP7") (pin "TP") (pinfunction "TP_TP") (pintype "input"))
      (node (ref "U1") (pin "5") (pinfunction "DI(IO0)_5") (pintype "bidirectional"))
      (node (ref "U2") (pin "7") (pinfunction "IO7_7") (pintype "bidirectional"))
    )
    (net (code "20") (name "Net-(CHG_LED-PadC)") (class "Default")
      (node (ref "CHG_LED") (pin "C") (pinfunction "C_C") (pintype "passive"))
      (node (ref "R1_BAT") (pin "1") (pinfunction "1_1") (pintype "passive"))
    )
    (net (code "21") (name "Net-(D2-CATHODE)") (class "Default")
      (node (ref "C1_BAT1") (pin "1") (pinfunction "1_1") (pintype "passive"))
      (node (ref "D2") (pin "1") (pinfunction "CATHODE_1") (pintype "bidirectional"))
      (node (ref "IC4") (pin "1") (pinfunction "VIN_1") (pintype "bidirectional"))
      (node (ref "IC4") (pin "3") (pinfunction "CE_3") (pintype "bidirectional"))
      (node (ref "Q1") (pin "2") (pinfunction "S_2") (pintype "bidirectional"))
    )
    (net (code "22") (name "Net-(D3-A)") (class "Default")
      (node (ref "C4") (pin "1") (pinfunction "1_1") (pintype "passive"))
      (node (ref "D3") (pin "2") (pinfunction "A_2") (pintype "bidirectional"))
      (node (ref "D4") (pin "1") (pinfunction "K_1") (pintype "bidirectional"))
    )
    (net (code "23") (name "Net-(D7-CATHODE)") (class "Default")
      (node (ref "D7") (pin "1") (pinfunction "CATHODE_1") (pintype "bidirectional"))
      (node (ref "R_CAPACITOR") (pin "2") (pinfunction "2_2") (pintype "passive"))
    )
    (net (code "24") (name "Net-(EPD_C1-Pad2)") (class "Default")
      (node (ref "EPD_C1") (pin "2") (pinfunction "2_2") (pintype "passive"))
      (node (ref "J1") (pin "4") (pinfunction "4_4") (pintype "bidirectional"))
    )
    (net (code "25") (name "Net-(EPD_C2-Pad2)") (class "Default")
      (node (ref "EPD_C2") (pin "2") (pinfunction "2_2") (pintype "passive"))
      (node (ref "J1") (pin "5") (pinfunction "5_5") (pintype "bidirectional"))
    )
    (net (code "26") (name "Net-(EPD_C6-Pad2)") (class "Default")
      (node (ref "EPD_C6") (pin "2") (pinfunction "2_2") (pintype "passive"))
      (node (ref "J1") (pin "18") (pinfunction "18_18") (pintype "bidirectional"))
    )
    (net (code "27") (name "Net-(EPD_C7-Pad2)") (class "Default")
      (node (ref "EPD_C7") (pin "2") (pinfunction "2_2") (pintype "passive"))
      (node (ref "J1") (pin "19") (pinfunction "19_19") (pintype "bidirectional"))
    )
    (net (code "28") (name "Net-(EPD_C8-Pad2)") (class "Default")
      (node (ref "EPD_C8") (pin "2") (pinfunction "2_2") (pintype "passive"))
      (node (ref "J1") (pin "20") (pinfunction "20_20") (pintype "bidirectional"))
    )
    (net (code "29") (name "Net-(EPD_C10-Pad2)") (class "Default")
      (node (ref "EPD_C10") (pin "2") (pinfunction "2_2") (pintype "passive"))
      (node (ref "J1") (pin "22") (pinfunction "22_22") (pintype "bidirectional"))
    )
    (net (code "30") (name "Net-(EPD_C12-Pad2)") (class "Default")
      (node (ref "EPD_C12") (pin "2") (pinfunction "2_2") (pintype "passive"))
      (node (ref "J1") (pin "24") (pinfunction "24_24") (pintype "bidirectional"))
    )
    (net (code "31") (name "Net-(IC1-CT)") (class "Default")
      (node (ref "C_DELAY") (pin "1") (pinfunction "1_1") (pintype "passive"))
      (node (ref "IC1") (pin "5") (pinfunction "CT_5") (pintype "bidirectional"))
    )
    (net (code "32") (name "Net-(J2-PadA5)") (class "Default")
      (node (ref "J2") (pin "A5") (pinfunction "A5_A5") (pintype "bidirectional"))
      (node (ref "R2-USB1") (pin "2") (pinfunction "2_2") (pintype "passive"))
    )
    (net (code "33") (name "Net-(J2-PadB5)") (class "Default")
      (node (ref "J2") (pin "B5") (pinfunction "B5_B5") (pintype "bidirectional"))
      (node (ref "R2-USB") (pin "1") (pinfunction "1_1") (pintype "passive"))
    )
    (net (code "34") (name "Net-(MCP73831-PROG)") (class "Default")
      (node (ref "MCP73831") (pin "5") (pinfunction "PROG_5") (pintype "input"))
      (node (ref "R2_BAT") (pin "2") (pinfunction "2_2") (pintype "passive"))
    )
    (net (code "35") (name "Net-(MCP73831-STAT)") (class "Default")
      (node (ref "MCP73831") (pin "1") (pinfunction "STAT_1") (pintype "output"))
      (node (ref "R1_BAT") (pin "2") (pinfunction "2_2") (pintype "passive"))
    )
    (net (code "36") (name "Net-(U2-IO8)") (class "Default")
      (node (ref "R1") (pin "1") (pinfunction "1_1") (pintype "passive"))
      (node (ref "U2") (pin "10") (pinfunction "IO8_10") (pintype "bidirectional"))
    )
    (net (code "37") (name "PREVGH") (class "Default")
      (node (ref "D5") (pin "1") (pinfunction "K_1") (pintype "bidirectional"))
      (node (ref "EPD_C9") (pin "2") (pinfunction "2_2") (pintype "passive"))
      (node (ref "J1") (pin "21") (pinfunction "21_21") (pintype "bidirectional"))
    )
    (net (code "38") (name "PREVGL") (class "Default")
      (node (ref "D4") (pin "2") (pinfunction "A_2") (pintype "bidirectional"))
      (node (ref "EPD_C11") (pin "2") (pinfunction "2_2") (pintype "passive"))
      (node (ref "J1") (pin "23") (pinfunction "23_23") (pintype "bidirectional"))
    )
    (net (code "39") (name "RESE") (class "Default")
      (node (ref "J1") (pin "3") (pinfunction "3_3") (pintype "bidirectional"))
      (node (ref "Q3") (pin "2") (pinfunction "S_2") (pintype "bidirectional"))
      (node (ref "R3") (pin "2") (pinfunction "2_2") (pintype "passive"))
    )
    (net (code "40") (name "RESE'") (class "Default")
      (node (ref "R2") (pin "2") (pinfunction "2_2") (pintype "passive"))
      (node (ref "R3") (pin "1") (pinfunction "1_1") (pintype "passive"))
      (node (ref "SJ1") (pin "2") (pinfunction "2_2") (pintype "passive"))
    )
    (net (code "41") (name "RESET") (class "Default")
      (node (ref "C5") (pin "1") (pinfunction "1_1") (pintype "passive"))
      (node (ref "IC1") (pin "1") (pinfunction "VOUT_1") (pintype "bidirectional"))
      (node (ref "RESET_BUTTON") (pin "4") (pinfunction "4_4") (pintype "passive"))
      (node (ref "R_RESET") (pin "1") (pinfunction "1_1") (pintype "passive"))
      (node (ref "U2") (pin "3") (pinfunction "EN_3") (pintype "input"))
    )
    (net (code "42") (name "RTC_RST") (class "Default")
      (node (ref "U2") (pin "17") (pinfunction "IO19_17") (pintype "bidirectional"))
      (node (ref "U3") (pin "4") (pinfunction "~{RST}_4") (pintype "input"))
    )
    (net (code "43") (name "RX") (class "Default")
      (node (ref "TP2") (pin "TP") (pinfunction "TP_TP") (pintype "input"))
      (node (ref "U2") (pin "24") (pinfunction "RXD0/GPIO17_24") (pintype "bidirectional"))
    )
    (net (code "44") (name "SCK") (class "Default")
      (node (ref "D10") (pin "2") (pinfunction "2_2") (pintype "passive"))
      (node (ref "J1") (pin "13") (pinfunction "13_13") (pintype "bidirectional"))
      (node (ref "J4") (pin "P5") (pinfunction "CLK_P5") (pintype "bidirectional"))
      (node (ref "R6") (pin "1") (pinfunction "1_1") (pintype "passive"))
      (node (ref "TP8") (pin "TP") (pinfunction "TP_TP") (pintype "input"))
      (node (ref "U1") (pin "6") (pinfunction "CLK_6") (pintype "input"))
      (node (ref "U2") (pin "6") (pinfunction "IO6_6") (pintype "bidirectional"))
    )
    (net (code "45") (name "SCL") (class "Default")
      (node (ref "J3") (pin "4") (pinfunction "4_4") (pintype "passive"))
      (node (ref "R2-PINH") (pin "1") (pinfunction "1_1") (pintype "passive"))
      (node (ref "SENSOR2") (pin "4") (pinfunction "SCK_4") (pintype "input"))
      (node (ref "U2") (pin "20") (pinfunction "IO22_20") (pintype "bidirectional"))
      (node (ref "U3") (pin "16") (pinfunction "SCL_16") (pintype "input"))
      (node (ref "U4") (pin "7") (pinfunction "SCL_7") (pintype "input"))
    )
    (net (code "46") (name "SDA") (class "Default")
      (node (ref "J3") (pin "3") (pinfunction "3_3") (pintype "passive"))
      (node (ref "R1_PINH") (pin "1") (pinfunction "1_1") (pintype "passive"))
      (node (ref "SENSOR2") (pin "3") (pinfunction "SDI_3") (pintype "bidirectional"))
      (node (ref "U2") (pin "19") (pinfunction "IO21_19") (pintype "bidirectional"))
      (node (ref "U3") (pin "15") (pinfunction "SDA_15") (pintype "bidirectional"))
      (node (ref "U4") (pin "8") (pinfunction "SDA_8") (pintype "bidirectional"))
    )
    (net (code "47") (name "SRC") (class "Default")
      (node (ref "C4") (pin "2") (pinfunction "2_2") (pintype "passive"))
      (node (ref "D5") (pin "2") (pinfunction "A_2") (pintype "bidirectional"))
      (node (ref "L1") (pin "1") (pinfunction "1_1") (pintype "passive"))
      (node (ref "Q3") (pin "3") (pinfunction "D_3") (pintype "bidirectional"))
    )
    (net (code "48") (name "SS_SD") (class "Default")
      (node (ref "D8") (pin "2") (pinfunction "2_2") (pintype "passive"))
      (node (ref "J4") (pin "P2") (pinfunction "CD/DAT3_P2") (pintype "bidirectional"))
      (node (ref "R10") (pin "1") (pinfunction "1_1") (pintype "passive"))
      (node (ref "U2") (pin "4") (pinfunction "IO4_4") (pintype "bidirectional"))
    )
    (net (code "49") (name "TX") (class "Default")
      (node (ref "TP1") (pin "TP") (pinfunction "TP_TP") (pintype "input"))
      (node (ref "U2") (pin "25") (pinfunction "TXD0/GPIO16_25") (pintype "bidirectional"))
    )
    (net (code "50") (name "USB_D+") (class "Default")
      (node (ref "D1") (pin "1") (pinfunction "I/O1_1_1") (pintype "bidirectional"))
      (node (ref "U2") (pin "14") (pinfunction "IO13_14") (pintype "bidirectional"))
    )
    (net (code "51") (name "USB_D-") (class "Default")
      (node (ref "D1") (pin "3") (pinfunction "I/O2_1_3") (pintype "bidirectional"))
      (node (ref "U2") (pin "13") (pinfunction "IO12_13") (pintype "bidirectional"))
    )
    (net (code "52") (name "VBAT") (class "Default")
      (node (ref "C2_BAT") (pin "1") (pinfunction "1_1") (pintype "passive"))
      (node (ref "MCP73831") (pin "3") (pinfunction "VBAT_3") (pintype "power_in"))
      (node (ref "Q1") (pin "3") (pinfunction "D_3") (pintype "bidirectional"))
      (node (ref "TP3") (pin "TP") (pinfunction "TP_TP") (pintype "input"))
      (node (ref "U4") (pin "2") (pinfunction "CELL_2") (pintype "power_in"))
      (node (ref "U4") (pin "3") (pinfunction "VDD_3") (pintype "power_in"))
    )
    (net (code "53") (name "VBUS") (class "Default")
      (node (ref "C1_BAT") (pin "1") (pinfunction "1_1") (pintype "passive"))
      (node (ref "C4_USB") (pin "1") (pinfunction "1_1") (pintype "passive"))
      (node (ref "C5_USB") (pin "1") (pinfunction "1_1") (pintype "passive"))
      (node (ref "CHG_LED") (pin "A") (pinfunction "A_A") (pintype "passive"))
      (node (ref "D1") (pin "5") (pinfunction "VBUS_5") (pintype "bidirectional"))
      (node (ref "D2") (pin "2") (pinfunction "ANODE_2") (pintype "bidirectional"))
      (node (ref "MCP73831") (pin "4") (pinfunction "VIN_4") (pintype "power_in"))
      (node (ref "PFMF.050.1") (pin "2") (pinfunction "2_2") (pintype "passive"))
      (node (ref "Q1") (pin "1") (pinfunction "G_1") (pintype "bidirectional"))
      (node (ref "R1_PWRUSB") (pin "2") (pinfunction "2_2") (pintype "passive"))
      (node (ref "TP14") (pin "TP") (pinfunction "TP_TP") (pintype "input"))
    )
    (net (code "54") (name "VRTC") (class "Default")
      (node (ref "C10_SUPERCAP") (pin "2") (pinfunction "2_2") (pintype "passive"))
      (node (ref "C8") (pin "1") (pinfunction "1_1") (pintype "passive"))
      (node (ref "R_CAPACITOR") (pin "1") (pinfunction "1_1") (pintype "passive"))
      (node (ref "U3") (pin "14") (pinfunction "VBAT_14") (pintype "power_in"))
    )
    (net (code "55") (name "VUSB") (class "Default")
      (node (ref "J2") (pin "A4") (pinfunction "A4_A4") (pintype "bidirectional"))
      (node (ref "J2") (pin "A9") (pinfunction "A9_A9") (pintype "bidirectional"))
      (node (ref "J2") (pin "B4") (pinfunction "B4_B4") (pintype "bidirectional"))
      (node (ref "J2") (pin "B9") (pinfunction "B9_B9") (pintype "bidirectional"))
      (node (ref "PFMF.050.1") (pin "1") (pinfunction "1_1") (pintype "passive"))
    )
    (net (code "56") (name "unconnected-(BOOT_BUTTON-Pad3)") (class "Default")
      (node (ref "BOOT_BUTTON") (pin "3") (pinfunction "3_3") (pintype "passive"))
    )
    (net (code "57") (name "unconnected-(CHANGE_BUTTON-Pad3)") (class "Default")
      (node (ref "CHANGE_BUTTON") (pin "3") (pinfunction "3_3") (pintype "passive"))
    )
    (net (code "58") (name "unconnected-(IC1-NC-Pad4)") (class "Default")
      (node (ref "IC1") (pin "4") (pinfunction "NC_4") (pintype "no_connect"))
    )
    (net (code "59") (name "unconnected-(IC4-NC-Pad4)") (class "Default")
      (node (ref "IC4") (pin "4") (pinfunction "NC_4") (pintype "no_connect"))
    )
    (net (code "60") (name "unconnected-(J1-Pad1)") (class "Default")
      (node (ref "J1") (pin "1") (pinfunction "1_1") (pintype "bidirectional"))
    )
    (net (code "61") (name "unconnected-(J1-Pad6)") (class "Default")
      (node (ref "J1") (pin "6") (pinfunction "6_6") (pintype "bidirectional"))
    )
    (net (code "62") (name "unconnected-(J1-Pad7)") (class "Default")
      (node (ref "J1") (pin "7") (pinfunction "7_7") (pintype "bidirectional"))
    )
    (net (code "63") (name "unconnected-(J2-PadA8)") (class "Default")
      (node (ref "J2") (pin "A8") (pinfunction "A8_A8") (pintype "bidirectional"))
    )
    (net (code "64") (name "unconnected-(J2-PadB8)") (class "Default")
      (node (ref "J2") (pin "B8") (pinfunction "B8_B8") (pintype "bidirectional"))
    )
    (net (code "65") (name "unconnected-(J4-DAT1-PadP8)") (class "Default")
      (node (ref "J4") (pin "P8") (pinfunction "DAT1_P8") (pintype "bidirectional"))
    )
    (net (code "66") (name "unconnected-(J4-DAT2-PadP1)") (class "Default")
      (node (ref "J4") (pin "P1") (pinfunction "DAT2_P1") (pintype "bidirectional"))
    )
    (net (code "67") (name "unconnected-(J4-DETECTION_1-PadS1)") (class "Default")
      (node (ref "J4") (pin "S1") (pinfunction "DETECTION_1_S1") (pintype "bidirectional"))
    )
    (net (code "68") (name "unconnected-(J4-DETECTION_2-PadS2)") (class "Default")
      (node (ref "J4") (pin "S2") (pinfunction "DETECTION_2_S2") (pintype "bidirectional"))
    )
    (net (code "69") (name "unconnected-(RESET_BUTTON-Pad3)") (class "Default")
      (node (ref "RESET_BUTTON") (pin "3") (pinfunction "3_3") (pintype "passive"))
    )
    (net (code "70") (name "unconnected-(U2-NC-Pad22)") (class "Default")
      (node (ref "U2") (pin "22") (pinfunction "NC_22") (pintype "no_connect"))
    )
    (net (code "71") (name "unconnected-(U4-~{ALERT}-Pad5)") (class "Default")
      (node (ref "U4") (pin "5") (pinfunction "~{ALERT}_5") (pintype "output"))
    )
  )
)
